# Arduino_Zero.net
KiCad netlist of a schematic drawn in EAGLE
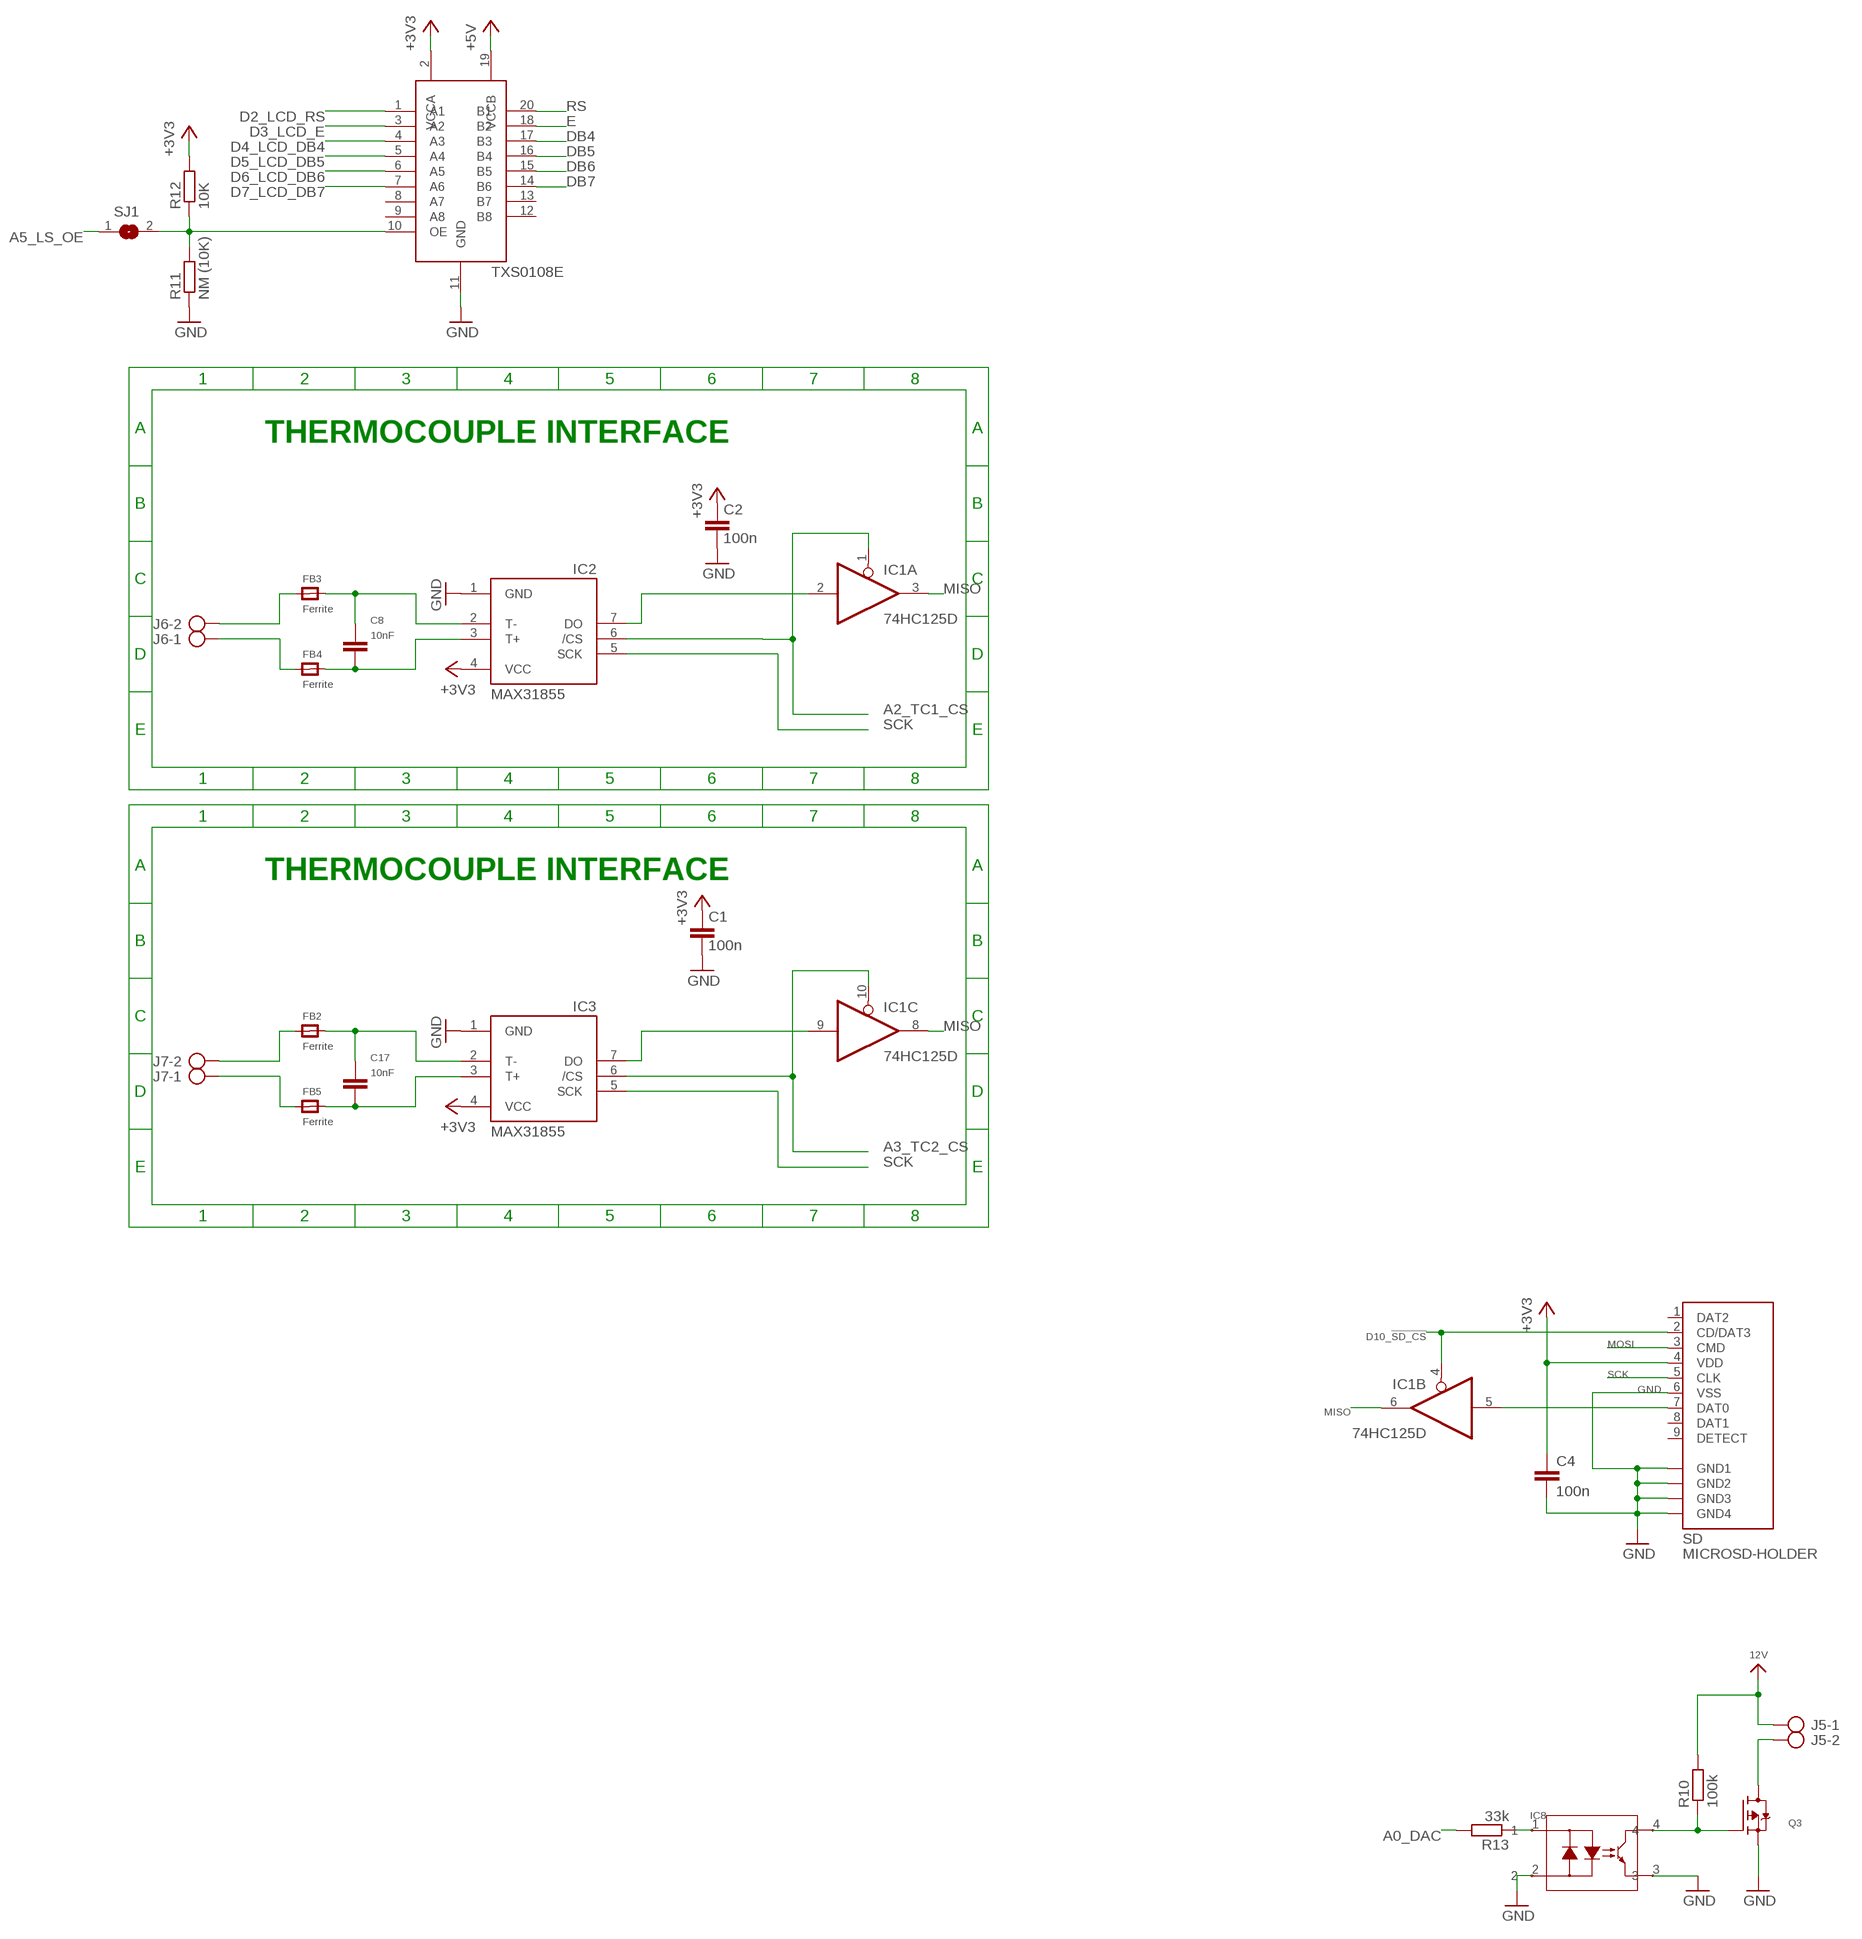
[diagram p0: schematic, sheet 1, part 1 of 2]
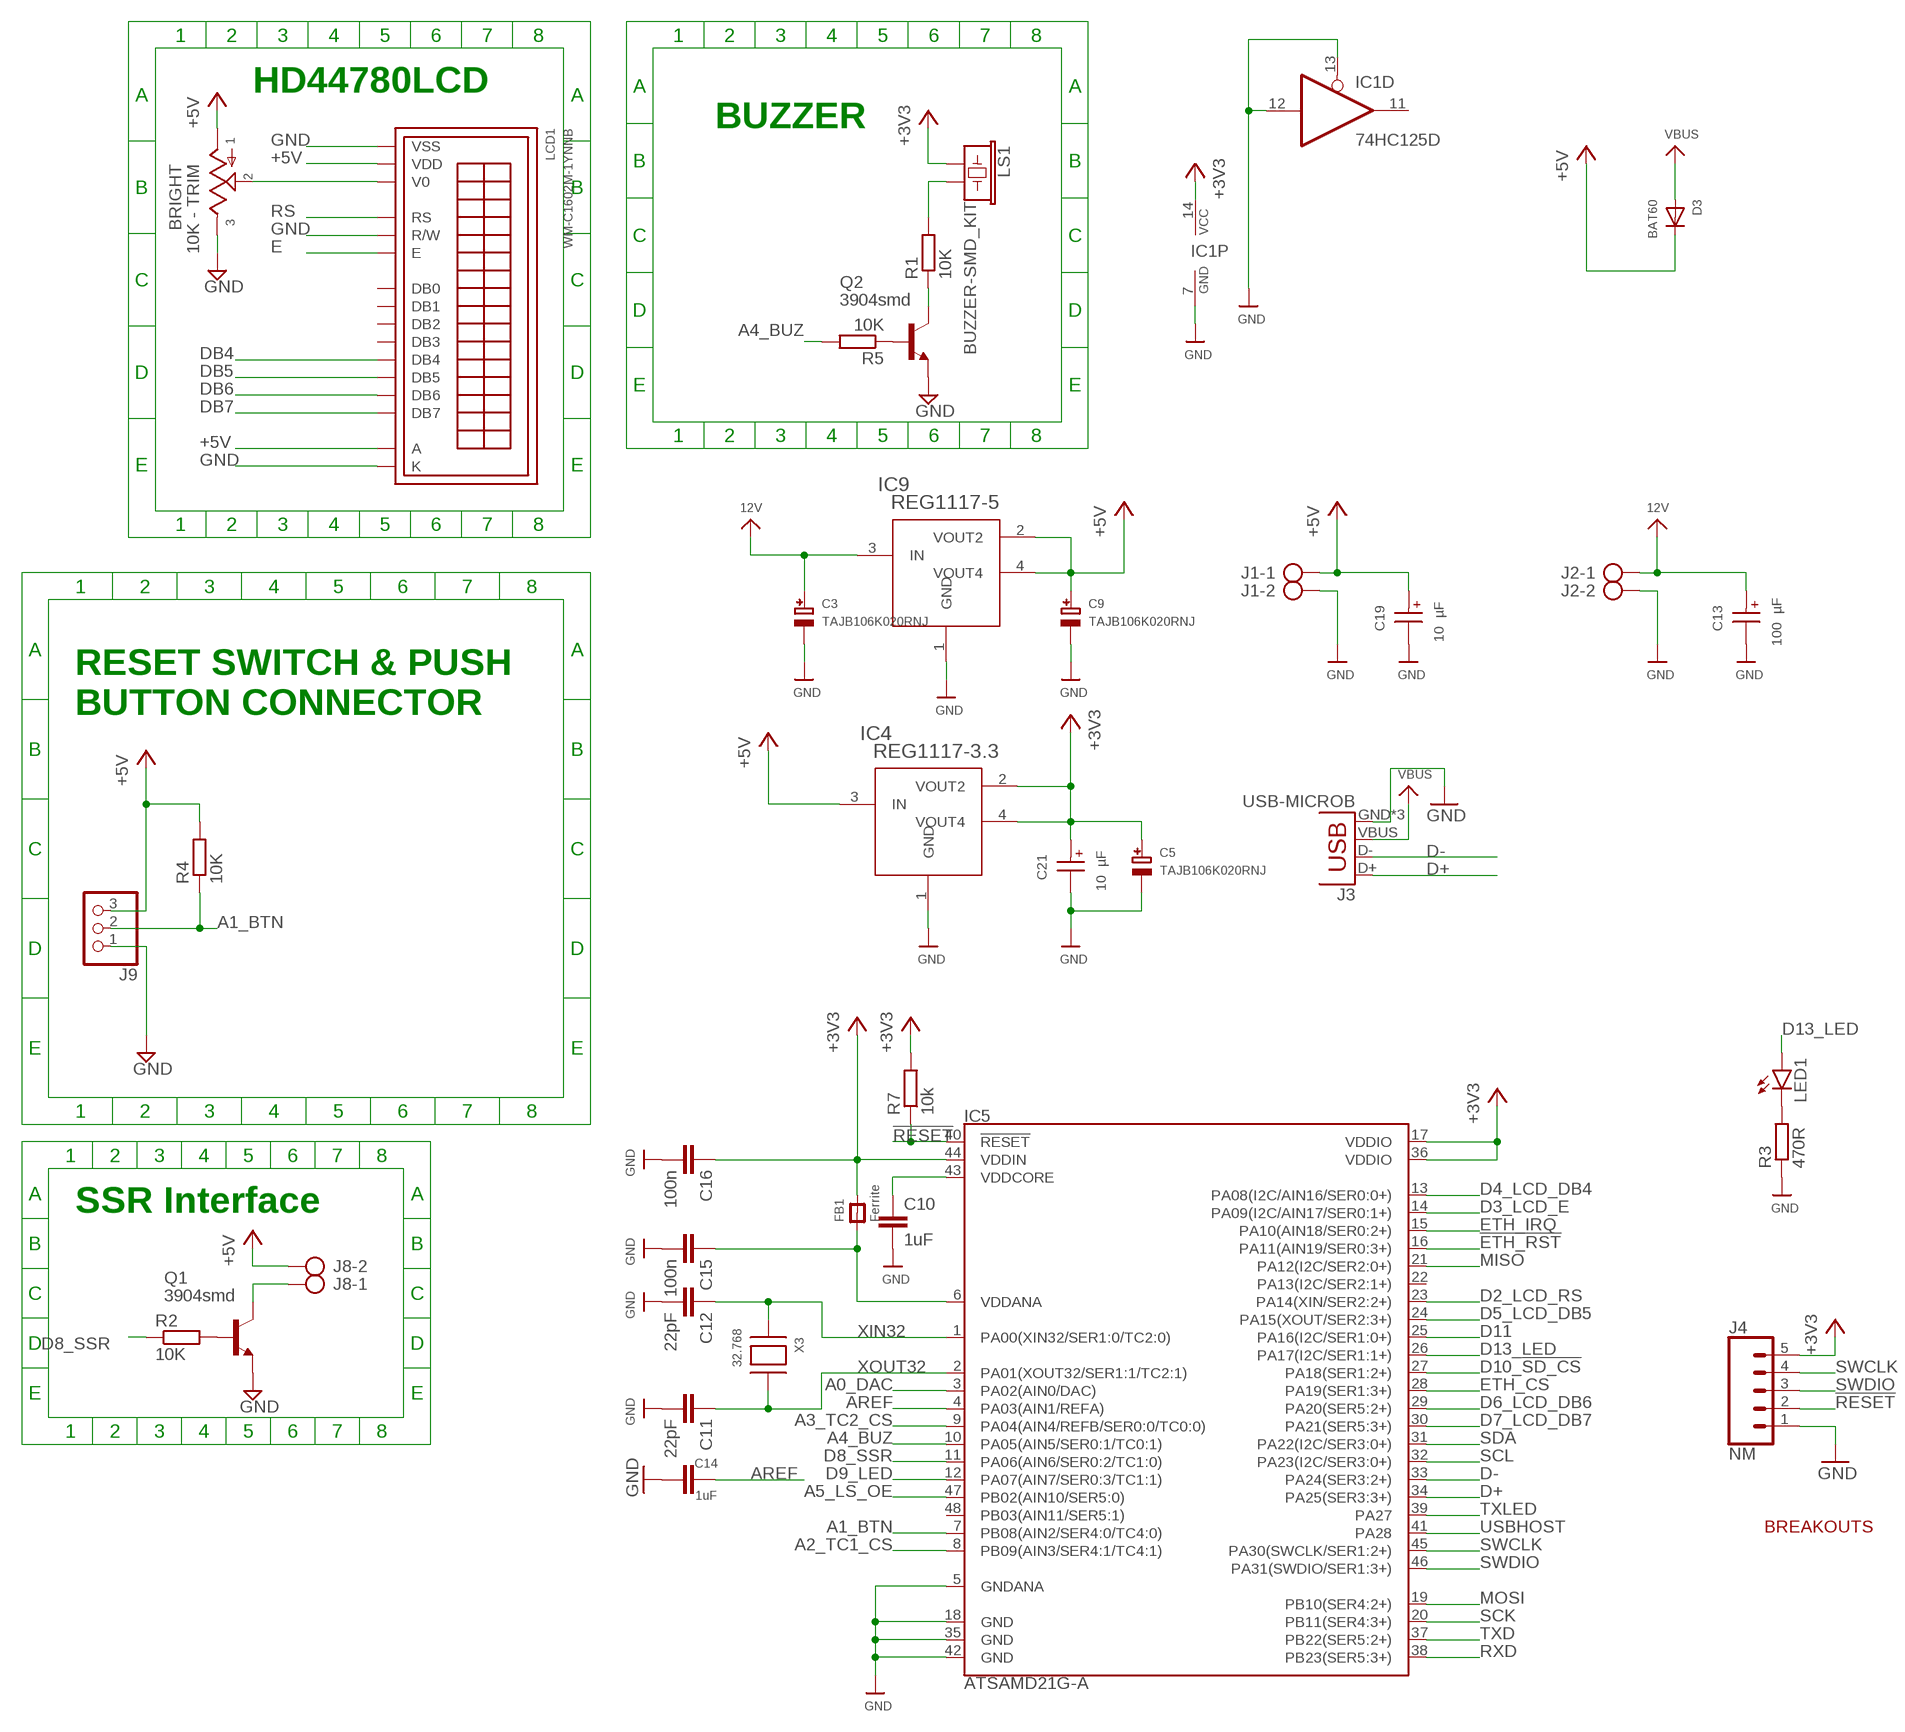
[diagram p1: schematic, sheet 1, part 2 of 2]

(export (version "E")
  (design (tool "Eeschema 10.0.6"))
  (components
    (comp (ref "BRIGHT")
      (value "10K - TRIM")
      (footprint "eagle-import:B25P")
      (libsource (lib "eagle-import") (part "POTTRIM"))
    )
    (comp (ref "C1")
      (value "100n")
      (footprint "eagle-import:C0603K")
      (libsource (lib "eagle-import") (part "C-EUC0603K"))
    )
    (comp (ref "C2")
      (value "100n")
      (footprint "eagle-import:C0603K")
      (libsource (lib "eagle-import") (part "C-EUC0603K"))
    )
    (comp (ref "C3")
      (value "TAJB106K020RNJ")
      (footprint "eagle-import:CAPMP3528X210N")
      (libsource (lib "eagle-import") (part "CAP_TANTALUM"))
    )
    (comp (ref "C4")
      (value "100n")
      (footprint "eagle-import:C0603K")
      (libsource (lib "eagle-import") (part "C-EUC0603K"))
    )
    (comp (ref "C5")
      (value "TAJB106K020RNJ")
      (footprint "eagle-import:CAPMP3528X210N")
      (libsource (lib "eagle-import") (part "CAP_TANTALUM"))
    )
    (comp (ref "C8")
      (value "10nF")
      (footprint "eagle-import:C0603K")
      (libsource (lib "eagle-import") (part "C-EUC0603K"))
    )
    (comp (ref "C9")
      (value "TAJB106K020RNJ")
      (footprint "eagle-import:CAPMP3528X210N")
      (libsource (lib "eagle-import") (part "CAP_TANTALUM"))
    )
    (comp (ref "C10")
      (value "1uF")
      (footprint "eagle-import:C0603K")
      (libsource (lib "eagle-import") (part "C-EUC0603K"))
    )
    (comp (ref "C11")
      (value "22pF")
      (footprint "eagle-import:C0603K")
      (libsource (lib "eagle-import") (part "C-EUC0603K"))
    )
    (comp (ref "C12")
      (value "22pF")
      (footprint "eagle-import:C0603K")
      (libsource (lib "eagle-import") (part "C-EUC0603K"))
    )
    (comp (ref "C13")
      (value "100 µF")
      (footprint "eagle-import:WCAP-ASLI_6.3X7.7(DXL)")
      (libsource (lib "eagle-import") (part "WCAP-ASLI_6.3X7.7_865080545012"))
    )
    (comp (ref "C14")
      (value "1uF")
      (footprint "eagle-import:C0603K")
      (libsource (lib "eagle-import") (part "C-EUC0603K"))
    )
    (comp (ref "C15")
      (value "100n")
      (footprint "eagle-import:C0603K")
      (libsource (lib "eagle-import") (part "C-EUC0603K"))
    )
    (comp (ref "C16")
      (value "100n")
      (footprint "eagle-import:C0603K")
      (libsource (lib "eagle-import") (part "C-EUC0603K"))
    )
    (comp (ref "C17")
      (value "10nF")
      (footprint "eagle-import:C0603K")
      (libsource (lib "eagle-import") (part "C-EUC0603K"))
    )
    (comp (ref "C19")
      (value "10 µF")
      (footprint "eagle-import:WCAP-ASLI_4X5.5(DXL)")
      (libsource (lib "eagle-import") (part "WCAP-ASLI_4X5.5_865080340001"))
    )
    (comp (ref "C21")
      (value "10 µF")
      (footprint "eagle-import:WCAP-ASLI_4X5.5(DXL)")
      (libsource (lib "eagle-import") (part "WCAP-ASLI_4X5.5_865080340001"))
    )
    (comp (ref "D3")
      (value "BAT60")
      (footprint "eagle-import:SOD323")
      (libsource (lib "eagle-import") (part "DIODESOD-323-3D"))
    )
    (comp (ref "FB1")
      (value "Ferrite")
      (footprint "eagle-import:BEADC3216X100N")
      (libsource (lib "eagle-import") (part "FERRITEBEAD"))
    )
    (comp (ref "FB2")
      (value "Ferrite")
      (footprint "eagle-import:BEADC3216X100N")
      (libsource (lib "eagle-import") (part "FERRITEBEAD"))
    )
    (comp (ref "FB3")
      (value "Ferrite")
      (footprint "eagle-import:BEADC3216X100N")
      (libsource (lib "eagle-import") (part "FERRITEBEAD"))
    )
    (comp (ref "FB4")
      (value "Ferrite")
      (footprint "eagle-import:BEADC3216X100N")
      (libsource (lib "eagle-import") (part "FERRITEBEAD"))
    )
    (comp (ref "FB5")
      (value "Ferrite")
      (footprint "eagle-import:BEADC3216X100N")
      (libsource (lib "eagle-import") (part "FERRITEBEAD"))
    )
    (comp (ref "IC1")
      (value "74HC125D")
      (footprint "eagle-import:SO14")
      (libsource (lib "eagle-import") (part "74125DHC"))
    )
    (comp (ref "IC2")
      (value "MAX31855")
      (footprint "eagle-import:SO08")
      (libsource (lib "eagle-import") (part "MAX6675"))
    )
    (comp (ref "IC3")
      (value "MAX31855")
      (footprint "eagle-import:SO08")
      (libsource (lib "eagle-import") (part "MAX6675"))
    )
    (comp (ref "IC4")
      (value "REG1117-3.3")
      (footprint "eagle-import:DCY0004A_N")
      (fields
        (field (name "MANUFACTURER_PART_NUMBER") "TLV1117-33CDCYR")
        (field (name "COPYRIGHT") "Copyright (C) 2022 Ultra Librarian. All rights reserved.")
      )
      (libsource (lib "eagle-import") (part "REG1117-5"))
    )
    (comp (ref "IC5")
      (value "ATSAMD21G-A")
      (footprint "eagle-import:TQFP-48")
      (libsource (lib "eagle-import") (part "ATSAMD21G-A"))
    )
    (comp (ref "IC7")
      (value "TXS0108E")
      (footprint "eagle-import:TSSOP20")
      (libsource (lib "eagle-import") (part "TXS0108E"))
    )
    (comp (ref "IC8")
      (value "TLP283")
      (footprint "eagle-import:SO4_TOS")
      (fields
        (field (name "MANUFACTURER_PART_NUMBER") "TLP292")
        (field (name "COPYRIGHT") "Copyright (C) 2022 Ultra Librarian. All rights reserved.")
      )
      (libsource (lib "eagle-import") (part "TLP292"))
    )
    (comp (ref "IC9")
      (value "REG1117-5")
      (footprint "eagle-import:DCY0004A_N")
      (fields
        (field (name "MANUFACTURER_PART_NUMBER") "TLV1117-33CDCYR")
        (field (name "COPYRIGHT") "Copyright (C) 2022 Ultra Librarian. All rights reserved.")
      )
      (libsource (lib "eagle-import") (part "REG1117-5"))
    )
    (comp (ref "J1")
      (value "AK500/2ASD")
      (footprint "eagle-import:AK500_2")
      (libsource (lib "eagle-import") (part "AK500/2ASD"))
    )
    (comp (ref "J2")
      (value "AK500/2ASD")
      (footprint "eagle-import:AK500_2")
      (libsource (lib "eagle-import") (part "AK500/2ASD"))
    )
    (comp (ref "J3")
      (value "USB-MICROB")
      (footprint "eagle-import:USB-MICROB")
      (libsource (lib "eagle-import") (part "USB-MICROB"))
    )
    (comp (ref "J4")
      (value "NM")
      (footprint "eagle-import:1X05_1.27MM")
      (libsource (lib "eagle-import") (part "CONN_051.27MM"))
    )
    (comp (ref "J5")
      (value "AK500/2ASD")
      (footprint "eagle-import:AK500_2")
      (libsource (lib "eagle-import") (part "AK500/2ASD"))
    )
    (comp (ref "J6")
      (value "AK500/2ASD")
      (footprint "eagle-import:AK500_2")
      (libsource (lib "eagle-import") (part "AK500/2ASD"))
    )
    (comp (ref "J7")
      (value "AK500/2ASD")
      (footprint "eagle-import:AK500_2")
      (libsource (lib "eagle-import") (part "AK500/2ASD"))
    )
    (comp (ref "J8")
      (value "AK500/2ASD")
      (footprint "eagle-import:AK500_2")
      (libsource (lib "eagle-import") (part "AK500/2ASD"))
    )
    (comp (ref "J9")
      (value "PINHD-1X3")
      (footprint "eagle-import:1X03")
      (libsource (lib "eagle-import") (part "PINHD-1X3"))
    )
    (comp (ref "LCD1")
      (value "WM-C1602M-1YNNB")
      (footprint "eagle-import:LCD_2")
      (libsource (lib "eagle-import") (part "WM-C1602M-1YNNB"))
    )
    (comp (ref "LED1")
      (value "LEDCHIPLED_0805")
      (footprint "eagle-import:CHIPLED_0805")
      (libsource (lib "eagle-import") (part "LEDCHIPLED_0805"))
    )
    (comp (ref "LS1")
      (value "BUZZER-SMD_KIT")
      (footprint "eagle-import:BUZZER-CCV-KIT")
      (libsource (lib "eagle-import") (part "BUZZER-SMD_KIT"))
    )
    (comp (ref "Q1")
      (value "3904smd")
      (footprint "eagle-import:SOT23-BEC")
      (libsource (lib "eagle-import") (part "BC850SMD"))
    )
    (comp (ref "Q2")
      (value "3904smd")
      (footprint "eagle-import:SOT23-BEC")
      (libsource (lib "eagle-import") (part "BC850SMD"))
    )
    (comp (ref "Q3")
      (value "MOSFET-PWIDE")
      (footprint "eagle-import:SOT23-WIDE")
      (libsource (lib "eagle-import") (part "MOSFET-PWIDE"))
    )
    (comp (ref "R1")
      (value "10K")
      (footprint "eagle-import:R0603")
      (libsource (lib "eagle-import") (part "R-EU_R0603"))
    )
    (comp (ref "R2")
      (value "10K")
      (footprint "eagle-import:R0603")
      (libsource (lib "eagle-import") (part "R-EU_R0603"))
    )
    (comp (ref "R3")
      (value "470R")
      (footprint "eagle-import:R0603")
      (libsource (lib "eagle-import") (part "R-EU_R0603"))
    )
    (comp (ref "R4")
      (value "10K")
      (footprint "eagle-import:R0603")
      (libsource (lib "eagle-import") (part "R-EU_R0603"))
    )
    (comp (ref "R5")
      (value "10K")
      (footprint "eagle-import:R0603")
      (libsource (lib "eagle-import") (part "R-EU_R0603"))
    )
    (comp (ref "R7")
      (value "10k")
      (footprint "eagle-import:R0603")
      (libsource (lib "eagle-import") (part "R-EU_R0603"))
    )
    (comp (ref "R10")
      (value "100k")
      (footprint "eagle-import:R0603")
      (libsource (lib "eagle-import") (part "R-EU_R0603"))
    )
    (comp (ref "R11")
      (value "NM (10K)")
      (footprint "eagle-import:R0603")
      (libsource (lib "eagle-import") (part "R-EU_R0603"))
    )
    (comp (ref "R12")
      (value "10K")
      (footprint "eagle-import:R0603")
      (libsource (lib "eagle-import") (part "R-EU_R0603"))
    )
    (comp (ref "R13")
      (value "33k")
      (footprint "eagle-import:R0603")
      (libsource (lib "eagle-import") (part "R-EU_R0603"))
    )
    (comp (ref "SD")
      (value "MICROSD-HOLDER")
      (footprint "eagle-import:MICROSD-HOLDER-ALIEX")
      (libsource (lib "eagle-import") (part "MICROSD-HOLDER"))
    )
    (comp (ref "SJ1") (value "SJ") (footprint "eagle-import:SJ") (libsource (lib "eagle-import") (part "SJ")))
    (comp (ref "X3")
      (value "32.768")
      (footprint "eagle-import:XTAL3215")
      (libsource (lib "eagle-import") (part "XTAL-3.2X1.5"))
    )
  )
  (nets
    (net (code "1") (name "+3V3") (class "Default")
      (node (ref "C1") (pin "1") (pinfunction "1_1") (pintype "passive"))
      (node (ref "C16") (pin "1") (pinfunction "1_1") (pintype "passive"))
      (node (ref "C2") (pin "1") (pinfunction "1_1") (pintype "passive"))
      (node (ref "C21") (pin "1") (pinfunction "+_1") (pintype "passive"))
      (node (ref "C4") (pin "1") (pinfunction "1_1") (pintype "passive"))
      (node (ref "C5") (pin "1") (pinfunction "+_1") (pintype "passive"))
      (node (ref "FB1") (pin "2") (pinfunction "P$2_2") (pintype "passive"))
      (node (ref "IC1") (pin "14") (pinfunction "VCC_14") (pintype "power_in"))
      (node (ref "IC2") (pin "4") (pinfunction "VCC_4") (pintype "power_in"))
      (node (ref "IC3") (pin "4") (pinfunction "VCC_4") (pintype "power_in"))
      (node (ref "IC4") (pin "2") (pinfunction "VOUT2_2") (pintype "power_in"))
      (node (ref "IC4") (pin "4") (pinfunction "VOUT4_4") (pintype "power_in"))
      (node (ref "IC5") (pin "17") (pinfunction "VDDIO_17") (pintype "bidirectional"))
      (node (ref "IC5") (pin "36") (pinfunction "VDDIO_36") (pintype "bidirectional"))
      (node (ref "IC5") (pin "44") (pinfunction "VDDIN_44") (pintype "bidirectional"))
      (node (ref "IC7") (pin "2") (pinfunction "VCCA_2") (pintype "bidirectional"))
      (node (ref "J4") (pin "5") (pinfunction "5_5") (pintype "passive"))
      (node (ref "LS1") (pin "+") (pinfunction "1_+") (pintype "passive"))
      (node (ref "R12") (pin "2") (pinfunction "2_2") (pintype "passive"))
      (node (ref "R7") (pin "2") (pinfunction "2_2") (pintype "passive"))
      (node (ref "SD") (pin "4") (pinfunction "VDD_4") (pintype "bidirectional"))
    )
    (net (code "2") (name "+5V") (class "Default")
      (node (ref "BRIGHT") (pin "1") (pinfunction "1_1") (pintype "passive"))
      (node (ref "C19") (pin "1") (pinfunction "+_1") (pintype "passive"))
      (node (ref "C9") (pin "1") (pinfunction "+_1") (pintype "passive"))
      (node (ref "D3") (pin "1") (pinfunction "C_1") (pintype "passive"))
      (node (ref "IC4") (pin "3") (pinfunction "IN_3") (pintype "power_in"))
      (node (ref "IC7") (pin "19") (pinfunction "VCCB_19") (pintype "bidirectional"))
      (node (ref "IC9") (pin "2") (pinfunction "VOUT2_2") (pintype "power_in"))
      (node (ref "IC9") (pin "4") (pinfunction "VOUT4_4") (pintype "power_in"))
      (node (ref "J1") (pin "1") (pinfunction "KL_1") (pintype "passive"))
      (node (ref "J8") (pin "2") (pinfunction "KL_2") (pintype "passive"))
      (node (ref "J9") (pin "3") (pinfunction "3_3") (pintype "passive"))
      (node (ref "LCD1") (pin "15") (pinfunction "A_15") (pintype "bidirectional"))
      (node (ref "LCD1") (pin "2") (pinfunction "VDD_2") (pintype "bidirectional"))
      (node (ref "R4") (pin "2") (pinfunction "2_2") (pintype "passive"))
    )
    (net (code "3") (name "/A0_DAC") (class "Default")
      (node (ref "IC5") (pin "3") (pinfunction "PA02(AIN0/DAC)_3") (pintype "bidirectional"))
      (node (ref "R13") (pin "2") (pinfunction "2_2") (pintype "passive"))
    )
    (net (code "4") (name "/A1_BTN") (class "Default")
      (node (ref "IC5") (pin "7") (pinfunction "PB08(AIN2/SER4:0/TC4:0)_7") (pintype "bidirectional"))
      (node (ref "J9") (pin "2") (pinfunction "2_2") (pintype "passive"))
      (node (ref "R4") (pin "1") (pinfunction "1_1") (pintype "passive"))
    )
    (net (code "5") (name "/A2_TC1_CS") (class "Default")
      (node (ref "IC1") (pin "1") (pinfunction "OE_1") (pintype "input"))
      (node (ref "IC2") (pin "6") (pinfunction "/CS_6") (pintype "input"))
      (node (ref "IC5") (pin "8") (pinfunction "PB09(AIN3/SER4:1/TC4:1)_8") (pintype "bidirectional"))
    )
    (net (code "6") (name "/A3_TC2_CS") (class "Default")
      (node (ref "IC1") (pin "10") (pinfunction "OE_10") (pintype "input"))
      (node (ref "IC3") (pin "6") (pinfunction "/CS_6") (pintype "input"))
      (node (ref "IC5") (pin "9") (pinfunction "PA04(AIN4/REFB/SER0:0/TC0:0)_9") (pintype "bidirectional"))
    )
    (net (code "7") (name "/A4_BUZ") (class "Default")
      (node (ref "IC5") (pin "10") (pinfunction "PA05(AIN5/SER0:1/TC0:1)_10") (pintype "bidirectional"))
      (node (ref "R5") (pin "2") (pinfunction "2_2") (pintype "passive"))
    )
    (net (code "8") (name "/A5_LS_OE") (class "Default")
      (node (ref "IC5") (pin "47") (pinfunction "PB02(AIN10/SER5:0)_47") (pintype "bidirectional"))
      (node (ref "SJ1") (pin "1") (pinfunction "1_1") (pintype "passive"))
    )
    (net (code "9") (name "/AREF") (class "Default")
      (node (ref "C14") (pin "1") (pinfunction "1_1") (pintype "passive"))
      (node (ref "IC5") (pin "4") (pinfunction "PA03(AIN1/REFA)_4") (pintype "bidirectional"))
    )
    (net (code "10") (name "/D+") (class "Default")
      (node (ref "IC5") (pin "34") (pinfunction "PA25(SER3:3+)_34") (pintype "bidirectional"))
      (node (ref "J3") (pin "D+") (pinfunction "D+_D+") (pintype "bidirectional"))
    )
    (net (code "11") (name "/D-") (class "Default")
      (node (ref "IC5") (pin "33") (pinfunction "PA24(SER3:2+)_33") (pintype "bidirectional"))
      (node (ref "J3") (pin "D-") (pinfunction "D-_D-") (pintype "bidirectional"))
    )
    (net (code "12") (name "/D2_LCD_RS") (class "Default")
      (node (ref "IC5") (pin "23") (pinfunction "PA14(XIN/SER2:2+)_23") (pintype "bidirectional"))
      (node (ref "IC7") (pin "1") (pinfunction "A1_1") (pintype "bidirectional"))
    )
    (net (code "13") (name "/D3_LCD_E") (class "Default")
      (node (ref "IC5") (pin "14") (pinfunction "PA09(I2C/AIN17/SER0:1+)_14") (pintype "bidirectional"))
      (node (ref "IC7") (pin "3") (pinfunction "A2_3") (pintype "bidirectional"))
    )
    (net (code "14") (name "/D4_LCD_DB4") (class "Default")
      (node (ref "IC5") (pin "13") (pinfunction "PA08(I2C/AIN16/SER0:0+)_13") (pintype "bidirectional"))
      (node (ref "IC7") (pin "4") (pinfunction "A3_4") (pintype "bidirectional"))
    )
    (net (code "15") (name "/D5_LCD_DB5") (class "Default")
      (node (ref "IC5") (pin "24") (pinfunction "PA15(XOUT/SER2:3+)_24") (pintype "bidirectional"))
      (node (ref "IC7") (pin "5") (pinfunction "A4_5") (pintype "bidirectional"))
    )
    (net (code "16") (name "/D6_LCD_DB6") (class "Default")
      (node (ref "IC5") (pin "29") (pinfunction "PA20(SER5:2+)_29") (pintype "bidirectional"))
      (node (ref "IC7") (pin "6") (pinfunction "A5_6") (pintype "bidirectional"))
    )
    (net (code "17") (name "/D7_LCD_DB7") (class "Default")
      (node (ref "IC5") (pin "30") (pinfunction "PA21(SER5:3+)_30") (pintype "bidirectional"))
      (node (ref "IC7") (pin "7") (pinfunction "A6_7") (pintype "bidirectional"))
    )
    (net (code "18") (name "/D8_SSR") (class "Default")
      (node (ref "IC5") (pin "11") (pinfunction "PA06(AIN6/SER0:2/TC1:0)_11") (pintype "bidirectional"))
      (node (ref "R2") (pin "1") (pinfunction "1_1") (pintype "passive"))
    )
    (net (code "19") (name "/D9_LED") (class "Default")
      (node (ref "IC5") (pin "12") (pinfunction "PA07(AIN7/SER0:3/TC1:1)_12") (pintype "bidirectional"))
    )
    (net (code "20") (name "/D10_~{SD_CS}") (class "Default")
      (node (ref "IC1") (pin "4") (pinfunction "OE_4") (pintype "input"))
      (node (ref "IC5") (pin "27") (pinfunction "PA18(SER1:2+)_27") (pintype "bidirectional"))
      (node (ref "SD") (pin "2") (pinfunction "CD/DAT3_2") (pintype "bidirectional"))
    )
    (net (code "21") (name "/D11") (class "Default")
      (node (ref "IC5") (pin "25") (pinfunction "PA16(I2C/SER1:0+)_25") (pintype "bidirectional"))
    )
    (net (code "22") (name "/D13_LED") (class "Default")
      (node (ref "IC5") (pin "26") (pinfunction "PA17(I2C/SER1:1+)_26") (pintype "bidirectional"))
      (node (ref "LED1") (pin "A") (pinfunction "A_A") (pintype "passive"))
    )
    (net (code "23") (name "/DB4") (class "Default")
      (node (ref "IC7") (pin "17") (pinfunction "B3_17") (pintype "bidirectional"))
      (node (ref "LCD1") (pin "11") (pinfunction "DB4_11") (pintype "bidirectional"))
    )
    (net (code "24") (name "/DB5") (class "Default")
      (node (ref "IC7") (pin "16") (pinfunction "B4_16") (pintype "bidirectional"))
      (node (ref "LCD1") (pin "12") (pinfunction "DB5_12") (pintype "bidirectional"))
    )
    (net (code "25") (name "/DB6") (class "Default")
      (node (ref "IC7") (pin "15") (pinfunction "B5_15") (pintype "bidirectional"))
      (node (ref "LCD1") (pin "13") (pinfunction "DB6_13") (pintype "bidirectional"))
    )
    (net (code "26") (name "/DB7") (class "Default")
      (node (ref "IC7") (pin "14") (pinfunction "B6_14") (pintype "bidirectional"))
      (node (ref "LCD1") (pin "14") (pinfunction "DB7_14") (pintype "bidirectional"))
    )
    (net (code "27") (name "/E") (class "Default")
      (node (ref "IC7") (pin "18") (pinfunction "B2_18") (pintype "bidirectional"))
      (node (ref "LCD1") (pin "6") (pinfunction "E_6") (pintype "bidirectional"))
    )
    (net (code "28") (name "/ETH_CS") (class "Default")
      (node (ref "IC5") (pin "28") (pinfunction "PA19(SER1:3+)_28") (pintype "bidirectional"))
    )
    (net (code "29") (name "/ETH_IRQ") (class "Default")
      (node (ref "IC5") (pin "15") (pinfunction "PA10(AIN18/SER0:2+)_15") (pintype "bidirectional"))
    )
    (net (code "30") (name "/MISO") (class "Default")
      (node (ref "IC1") (pin "3") (pinfunction "O_3") (pintype "tri_state"))
      (node (ref "IC1") (pin "6") (pinfunction "O_6") (pintype "tri_state"))
      (node (ref "IC1") (pin "8") (pinfunction "O_8") (pintype "tri_state"))
      (node (ref "IC5") (pin "21") (pinfunction "PA12(I2C/SER2:0+)_21") (pintype "bidirectional"))
    )
    (net (code "31") (name "/MOSI") (class "Default")
      (node (ref "IC5") (pin "19") (pinfunction "PB10(SER4:2+)_19") (pintype "bidirectional"))
      (node (ref "SD") (pin "3") (pinfunction "CMD_3") (pintype "bidirectional"))
    )
    (net (code "32") (name "/RS") (class "Default")
      (node (ref "IC7") (pin "20") (pinfunction "B1_20") (pintype "bidirectional"))
      (node (ref "LCD1") (pin "4") (pinfunction "RS_4") (pintype "bidirectional"))
    )
    (net (code "33") (name "/RXD") (class "Default")
      (node (ref "IC5") (pin "38") (pinfunction "PB23(SER5:3+)_38") (pintype "bidirectional"))
    )
    (net (code "34") (name "/SCK") (class "Default")
      (node (ref "IC2") (pin "5") (pinfunction "SCK_5") (pintype "input"))
      (node (ref "IC3") (pin "5") (pinfunction "SCK_5") (pintype "input"))
      (node (ref "IC5") (pin "20") (pinfunction "PB11(SER4:3+)_20") (pintype "bidirectional"))
      (node (ref "SD") (pin "5") (pinfunction "CLK_5") (pintype "bidirectional"))
    )
    (net (code "35") (name "/SCL") (class "Default")
      (node (ref "IC5") (pin "32") (pinfunction "PA23(I2C/SER3:0+)_32") (pintype "bidirectional"))
    )
    (net (code "36") (name "/SDA") (class "Default")
      (node (ref "IC5") (pin "31") (pinfunction "PA22(I2C/SER3:0+)_31") (pintype "bidirectional"))
    )
    (net (code "37") (name "/SWCLK") (class "Default")
      (node (ref "IC5") (pin "45") (pinfunction "PA30(SWCLK/SER1:2+)_45") (pintype "bidirectional"))
      (node (ref "J4") (pin "4") (pinfunction "4_4") (pintype "passive"))
    )
    (net (code "38") (name "/SWDIO") (class "Default")
      (node (ref "IC5") (pin "46") (pinfunction "PA31(SWDIO/SER1:3+)_46") (pintype "bidirectional"))
      (node (ref "J4") (pin "3") (pinfunction "3_3") (pintype "passive"))
    )
    (net (code "39") (name "/TXD") (class "Default")
      (node (ref "IC5") (pin "37") (pinfunction "PB22(SER5:2+)_37") (pintype "bidirectional"))
    )
    (net (code "40") (name "/TXLED") (class "Default")
      (node (ref "IC5") (pin "39") (pinfunction "PA27_39") (pintype "bidirectional"))
    )
    (net (code "41") (name "/USBHOST") (class "Default")
      (node (ref "IC5") (pin "41") (pinfunction "PA28_41") (pintype "bidirectional"))
    )
    (net (code "42") (name "/XIN32") (class "Default")
      (node (ref "C12") (pin "1") (pinfunction "1_1") (pintype "passive"))
      (node (ref "IC5") (pin "1") (pinfunction "PA00(XIN32/SER1:0/TC2:0)_1") (pintype "bidirectional"))
      (node (ref "X3") (pin "P$1") (pinfunction "P$1_P$1") (pintype "bidirectional"))
    )
    (net (code "43") (name "/XOUT32") (class "Default")
      (node (ref "C11") (pin "1") (pinfunction "1_1") (pintype "passive"))
      (node (ref "IC5") (pin "2") (pinfunction "PA01(XOUT32/SER1:1/TC2:1)_2") (pintype "bidirectional"))
      (node (ref "X3") (pin "P$2") (pinfunction "P$2_P$2") (pintype "bidirectional"))
    )
    (net (code "44") (name "/~{ETH_RST}") (class "Default")
      (node (ref "IC5") (pin "16") (pinfunction "PA11(AIN19/SER0:3+)_16") (pintype "bidirectional"))
    )
    (net (code "45") (name "/~{RESET}") (class "Default")
      (node (ref "IC5") (pin "40") (pinfunction "~{RESET}_40") (pintype "bidirectional"))
      (node (ref "J4") (pin "2") (pinfunction "2_2") (pintype "passive"))
      (node (ref "R7") (pin "1") (pinfunction "1_1") (pintype "passive"))
    )
    (net (code "46") (name "12V") (class "Default")
      (node (ref "C13") (pin "1") (pinfunction "+_1") (pintype "passive"))
      (node (ref "C3") (pin "1") (pinfunction "+_1") (pintype "passive"))
      (node (ref "IC9") (pin "3") (pinfunction "IN_3") (pintype "power_in"))
      (node (ref "J2") (pin "1") (pinfunction "KL_1") (pintype "passive"))
      (node (ref "J5") (pin "1") (pinfunction "KL_1") (pintype "passive"))
      (node (ref "R10") (pin "2") (pinfunction "2_2") (pintype "passive"))
    )
    (net (code "47") (name "GND") (class "Default")
      (node (ref "BRIGHT") (pin "3") (pinfunction "3_3") (pintype "passive"))
      (node (ref "C1") (pin "2") (pinfunction "2_2") (pintype "passive"))
      (node (ref "C10") (pin "2") (pinfunction "2_2") (pintype "passive"))
      (node (ref "C11") (pin "2") (pinfunction "2_2") (pintype "passive"))
      (node (ref "C12") (pin "2") (pinfunction "2_2") (pintype "passive"))
      (node (ref "C13") (pin "2") (pinfunction "-_2") (pintype "passive"))
      (node (ref "C14") (pin "2") (pinfunction "2_2") (pintype "passive"))
      (node (ref "C15") (pin "2") (pinfunction "2_2") (pintype "passive"))
      (node (ref "C16") (pin "2") (pinfunction "2_2") (pintype "passive"))
      (node (ref "C19") (pin "2") (pinfunction "-_2") (pintype "passive"))
      (node (ref "C2") (pin "2") (pinfunction "2_2") (pintype "passive"))
      (node (ref "C21") (pin "2") (pinfunction "-_2") (pintype "passive"))
      (node (ref "C3") (pin "2") (pinfunction "-_2") (pintype "passive"))
      (node (ref "C4") (pin "2") (pinfunction "2_2") (pintype "passive"))
      (node (ref "C5") (pin "2") (pinfunction "-_2") (pintype "passive"))
      (node (ref "C9") (pin "2") (pinfunction "-_2") (pintype "passive"))
      (node (ref "IC1") (pin "12") (pinfunction "I_12") (pintype "input"))
      (node (ref "IC1") (pin "13") (pinfunction "OE_13") (pintype "input"))
      (node (ref "IC1") (pin "7") (pinfunction "GND_7") (pintype "power_in"))
      (node (ref "IC2") (pin "1") (pinfunction "GND_1") (pintype "power_in"))
      (node (ref "IC3") (pin "1") (pinfunction "GND_1") (pintype "power_in"))
      (node (ref "IC4") (pin "1") (pinfunction "GND_1") (pintype "power_in"))
      (node (ref "IC5") (pin "18") (pinfunction "GND_18") (pintype "bidirectional"))
      (node (ref "IC5") (pin "35") (pinfunction "GND_35") (pintype "bidirectional"))
      (node (ref "IC5") (pin "42") (pinfunction "GND_42") (pintype "bidirectional"))
      (node (ref "IC5") (pin "5") (pinfunction "GNDANA_5") (pintype "bidirectional"))
      (node (ref "IC7") (pin "11") (pinfunction "GND_11") (pintype "bidirectional"))
      (node (ref "IC8") (pin "2") (pinfunction "2_2") (pintype "passive"))
      (node (ref "IC8") (pin "3") (pinfunction "3_3") (pintype "passive"))
      (node (ref "IC9") (pin "1") (pinfunction "GND_1") (pintype "power_in"))
      (node (ref "J1") (pin "2") (pinfunction "KL_2") (pintype "passive"))
      (node (ref "J2") (pin "2") (pinfunction "KL_2") (pintype "passive"))
      (node (ref "J3") (pin "GND") (pinfunction "GND_GND") (pintype "bidirectional"))
      (node (ref "J3") (pin "MT1") (pinfunction "GND_MT1") (pintype "bidirectional"))
      (node (ref "J3") (pin "MT2") (pinfunction "GND_MT2") (pintype "bidirectional"))
      (node (ref "J4") (pin "1") (pinfunction "1_1") (pintype "passive"))
      (node (ref "J9") (pin "1") (pinfunction "1_1") (pintype "passive"))
      (node (ref "LCD1") (pin "1") (pinfunction "VSS_1") (pintype "bidirectional"))
      (node (ref "LCD1") (pin "16") (pinfunction "K_16") (pintype "bidirectional"))
      (node (ref "LCD1") (pin "5") (pinfunction "R/W_5") (pintype "bidirectional"))
      (node (ref "Q1") (pin "E") (pinfunction "E_E") (pintype "passive"))
      (node (ref "Q2") (pin "E") (pinfunction "E_E") (pintype "passive"))
      (node (ref "Q3") (pin "2") (pinfunction "S_2") (pintype "passive"))
      (node (ref "R11") (pin "1") (pinfunction "1_1") (pintype "passive"))
      (node (ref "R3") (pin "1") (pinfunction "1_1") (pintype "passive"))
      (node (ref "SD") (pin "6") (pinfunction "VSS_6") (pintype "bidirectional"))
      (node (ref "SD") (pin "P$1") (pinfunction "GND1_P$1") (pintype "bidirectional"))
      (node (ref "SD") (pin "P$2") (pinfunction "GND2_P$2") (pintype "bidirectional"))
      (node (ref "SD") (pin "P$3") (pinfunction "GND3_P$3") (pintype "bidirectional"))
      (node (ref "SD") (pin "P$4") (pinfunction "GND4_P$4") (pintype "bidirectional"))
    )
    (net (code "48") (name "Net-(FB1-P$1)") (class "Default")
      (node (ref "C15") (pin "1") (pinfunction "1_1") (pintype "passive"))
      (node (ref "FB1") (pin "1") (pinfunction "P$1_1") (pintype "passive"))
      (node (ref "IC5") (pin "6") (pinfunction "VDDANA_6") (pintype "bidirectional"))
    )
    (net (code "49") (name "Net-(FB2-P$1)") (class "Default")
      (node (ref "FB2") (pin "1") (pinfunction "P$1_1") (pintype "passive"))
      (node (ref "J7") (pin "2") (pinfunction "KL_2") (pintype "passive"))
    )
    (net (code "50") (name "Net-(FB2-P$2)") (class "Default")
      (node (ref "C17") (pin "1") (pinfunction "1_1") (pintype "passive"))
      (node (ref "FB2") (pin "2") (pinfunction "P$2_2") (pintype "passive"))
      (node (ref "IC3") (pin "2") (pinfunction "T-_2") (pintype "input"))
    )
    (net (code "51") (name "Net-(FB3-P$1)") (class "Default")
      (node (ref "FB3") (pin "1") (pinfunction "P$1_1") (pintype "passive"))
      (node (ref "J6") (pin "2") (pinfunction "KL_2") (pintype "passive"))
    )
    (net (code "52") (name "Net-(FB3-P$2)") (class "Default")
      (node (ref "C8") (pin "1") (pinfunction "1_1") (pintype "passive"))
      (node (ref "FB3") (pin "2") (pinfunction "P$2_2") (pintype "passive"))
      (node (ref "IC2") (pin "2") (pinfunction "T-_2") (pintype "input"))
    )
    (net (code "53") (name "Net-(FB4-P$1)") (class "Default")
      (node (ref "FB4") (pin "1") (pinfunction "P$1_1") (pintype "passive"))
      (node (ref "J6") (pin "1") (pinfunction "KL_1") (pintype "passive"))
    )
    (net (code "54") (name "Net-(FB4-P$2)") (class "Default")
      (node (ref "C8") (pin "2") (pinfunction "2_2") (pintype "passive"))
      (node (ref "FB4") (pin "2") (pinfunction "P$2_2") (pintype "passive"))
      (node (ref "IC2") (pin "3") (pinfunction "T+_3") (pintype "input"))
    )
    (net (code "55") (name "Net-(FB5-P$1)") (class "Default")
      (node (ref "FB5") (pin "1") (pinfunction "P$1_1") (pintype "passive"))
      (node (ref "J7") (pin "1") (pinfunction "KL_1") (pintype "passive"))
    )
    (net (code "56") (name "Net-(FB5-P$2)") (class "Default")
      (node (ref "C17") (pin "2") (pinfunction "2_2") (pintype "passive"))
      (node (ref "FB5") (pin "2") (pinfunction "P$2_2") (pintype "passive"))
      (node (ref "IC3") (pin "3") (pinfunction "T+_3") (pintype "input"))
    )
    (net (code "57") (name "Net-(IC1A-I)") (class "Default")
      (node (ref "IC1") (pin "2") (pinfunction "I_2") (pintype "input"))
      (node (ref "IC2") (pin "7") (pinfunction "DO_7") (pintype "output"))
    )
    (net (code "58") (name "Net-(IC1B-I)") (class "Default")
      (node (ref "IC1") (pin "5") (pinfunction "I_5") (pintype "input"))
      (node (ref "SD") (pin "7") (pinfunction "DAT0_7") (pintype "bidirectional"))
    )
    (net (code "59") (name "Net-(IC1C-I)") (class "Default")
      (node (ref "IC1") (pin "9") (pinfunction "I_9") (pintype "input"))
      (node (ref "IC3") (pin "7") (pinfunction "DO_7") (pintype "output"))
    )
    (net (code "60") (name "Net-(IC5-VDDCORE)") (class "Default")
      (node (ref "C10") (pin "1") (pinfunction "1_1") (pintype "passive"))
      (node (ref "IC5") (pin "43") (pinfunction "VDDCORE_43") (pintype "bidirectional"))
    )
    (net (code "61") (name "Net-(IC7-OE)") (class "Default")
      (node (ref "IC7") (pin "10") (pinfunction "OE_10") (pintype "bidirectional"))
      (node (ref "R11") (pin "2") (pinfunction "2_2") (pintype "passive"))
      (node (ref "R12") (pin "1") (pinfunction "1_1") (pintype "passive"))
      (node (ref "SJ1") (pin "2") (pinfunction "2_2") (pintype "passive"))
    )
    (net (code "62") (name "Net-(IC8-Pad1)") (class "Default")
      (node (ref "IC8") (pin "1") (pinfunction "1_1") (pintype "passive"))
      (node (ref "R13") (pin "1") (pinfunction "1_1") (pintype "passive"))
    )
    (net (code "63") (name "Net-(J5B-KL)") (class "Default")
      (node (ref "J5") (pin "2") (pinfunction "KL_2") (pintype "passive"))
      (node (ref "Q3") (pin "3") (pinfunction "D_3") (pintype "passive"))
    )
    (net (code "64") (name "Net-(J8A-KL)") (class "Default")
      (node (ref "J8") (pin "1") (pinfunction "KL_1") (pintype "passive"))
      (node (ref "Q1") (pin "C") (pinfunction "C_C") (pintype "passive"))
    )
    (net (code "65") (name "Net-(LCD1-V0)") (class "Default")
      (node (ref "BRIGHT") (pin "2") (pinfunction "2_2") (pintype "passive"))
      (node (ref "LCD1") (pin "3") (pinfunction "V0_3") (pintype "bidirectional"))
    )
    (net (code "66") (name "Net-(LED1-PadC)") (class "Default")
      (node (ref "LED1") (pin "C") (pinfunction "C_C") (pintype "passive"))
      (node (ref "R3") (pin "2") (pinfunction "2_2") (pintype "passive"))
    )
    (net (code "67") (name "Net-(LS1-2)") (class "Default")
      (node (ref "LS1") (pin "-") (pinfunction "2_-") (pintype "passive"))
      (node (ref "R1") (pin "2") (pinfunction "2_2") (pintype "passive"))
    )
    (net (code "68") (name "Net-(Q1-PadB)") (class "Default")
      (node (ref "Q1") (pin "B") (pinfunction "B_B") (pintype "passive"))
      (node (ref "R2") (pin "2") (pinfunction "2_2") (pintype "passive"))
    )
    (net (code "69") (name "Net-(Q2-PadB)") (class "Default")
      (node (ref "Q2") (pin "B") (pinfunction "B_B") (pintype "passive"))
      (node (ref "R5") (pin "1") (pinfunction "1_1") (pintype "passive"))
    )
    (net (code "70") (name "Net-(Q2-PadC)") (class "Default")
      (node (ref "Q2") (pin "C") (pinfunction "C_C") (pintype "passive"))
      (node (ref "R1") (pin "1") (pinfunction "1_1") (pintype "passive"))
    )
    (net (code "71") (name "Net-(Q3-G)") (class "Default")
      (node (ref "IC8") (pin "4") (pinfunction "4_4") (pintype "passive"))
      (node (ref "Q3") (pin "1") (pinfunction "G_1") (pintype "passive"))
      (node (ref "R10") (pin "1") (pinfunction "1_1") (pintype "passive"))
    )
    (net (code "72") (name "VBUS") (class "Default")
      (node (ref "D3") (pin "2") (pinfunction "A_2") (pintype "passive"))
      (node (ref "J3") (pin "VBUS") (pinfunction "VBUS_VBUS") (pintype "bidirectional"))
    )
    (net (code "73") (name "unconnected-(IC1D-O-Pad11)") (class "Default")
      (node (ref "IC1") (pin "11") (pinfunction "O_11") (pintype "tri_state"))
    )
    (net (code "74") (name "unconnected-(IC5-PA13(I2C{slash}SER2:1+)-Pad22)") (class "Default")
      (node (ref "IC5") (pin "22") (pinfunction "PA13(I2C/SER2:1+)_22") (pintype "bidirectional"))
    )
    (net (code "75") (name "unconnected-(IC5-PB03(AIN11{slash}SER5:1)-Pad48)") (class "Default")
      (node (ref "IC5") (pin "48") (pinfunction "PB03(AIN11/SER5:1)_48") (pintype "bidirectional"))
    )
    (net (code "76") (name "unconnected-(IC7-A7-Pad8)") (class "Default")
      (node (ref "IC7") (pin "8") (pinfunction "A7_8") (pintype "bidirectional"))
    )
    (net (code "77") (name "unconnected-(IC7-A8-Pad9)") (class "Default")
      (node (ref "IC7") (pin "9") (pinfunction "A8_9") (pintype "bidirectional"))
    )
    (net (code "78") (name "unconnected-(IC7-B7-Pad13)") (class "Default")
      (node (ref "IC7") (pin "13") (pinfunction "B7_13") (pintype "bidirectional"))
    )
    (net (code "79") (name "unconnected-(IC7-B8-Pad12)") (class "Default")
      (node (ref "IC7") (pin "12") (pinfunction "B8_12") (pintype "bidirectional"))
    )
    (net (code "80") (name "unconnected-(LCD1-DB0-Pad7)") (class "Default")
      (node (ref "LCD1") (pin "7") (pinfunction "DB0_7") (pintype "bidirectional"))
    )
    (net (code "81") (name "unconnected-(LCD1-DB1-Pad8)") (class "Default")
      (node (ref "LCD1") (pin "8") (pinfunction "DB1_8") (pintype "bidirectional"))
    )
    (net (code "82") (name "unconnected-(LCD1-DB2-Pad9)") (class "Default")
      (node (ref "LCD1") (pin "9") (pinfunction "DB2_9") (pintype "bidirectional"))
    )
    (net (code "83") (name "unconnected-(LCD1-DB3-Pad10)") (class "Default")
      (node (ref "LCD1") (pin "10") (pinfunction "DB3_10") (pintype "bidirectional"))
    )
    (net (code "84") (name "unconnected-(SD-DAT1-Pad8)") (class "Default")
      (node (ref "SD") (pin "8") (pinfunction "DAT1_8") (pintype "bidirectional"))
    )
    (net (code "85") (name "unconnected-(SD-DAT2-Pad1)") (class "Default")
      (node (ref "SD") (pin "1") (pinfunction "DAT2_1") (pintype "bidirectional"))
    )
    (net (code "86") (name "unconnected-(SD-DETECT-Pad9)") (class "Default")
      (node (ref "SD") (pin "9") (pinfunction "DETECT_9") (pintype "bidirectional"))
    )
  )
)
